# moisture_sensors.net
KiCad netlist of a schematic drawn in EAGLE
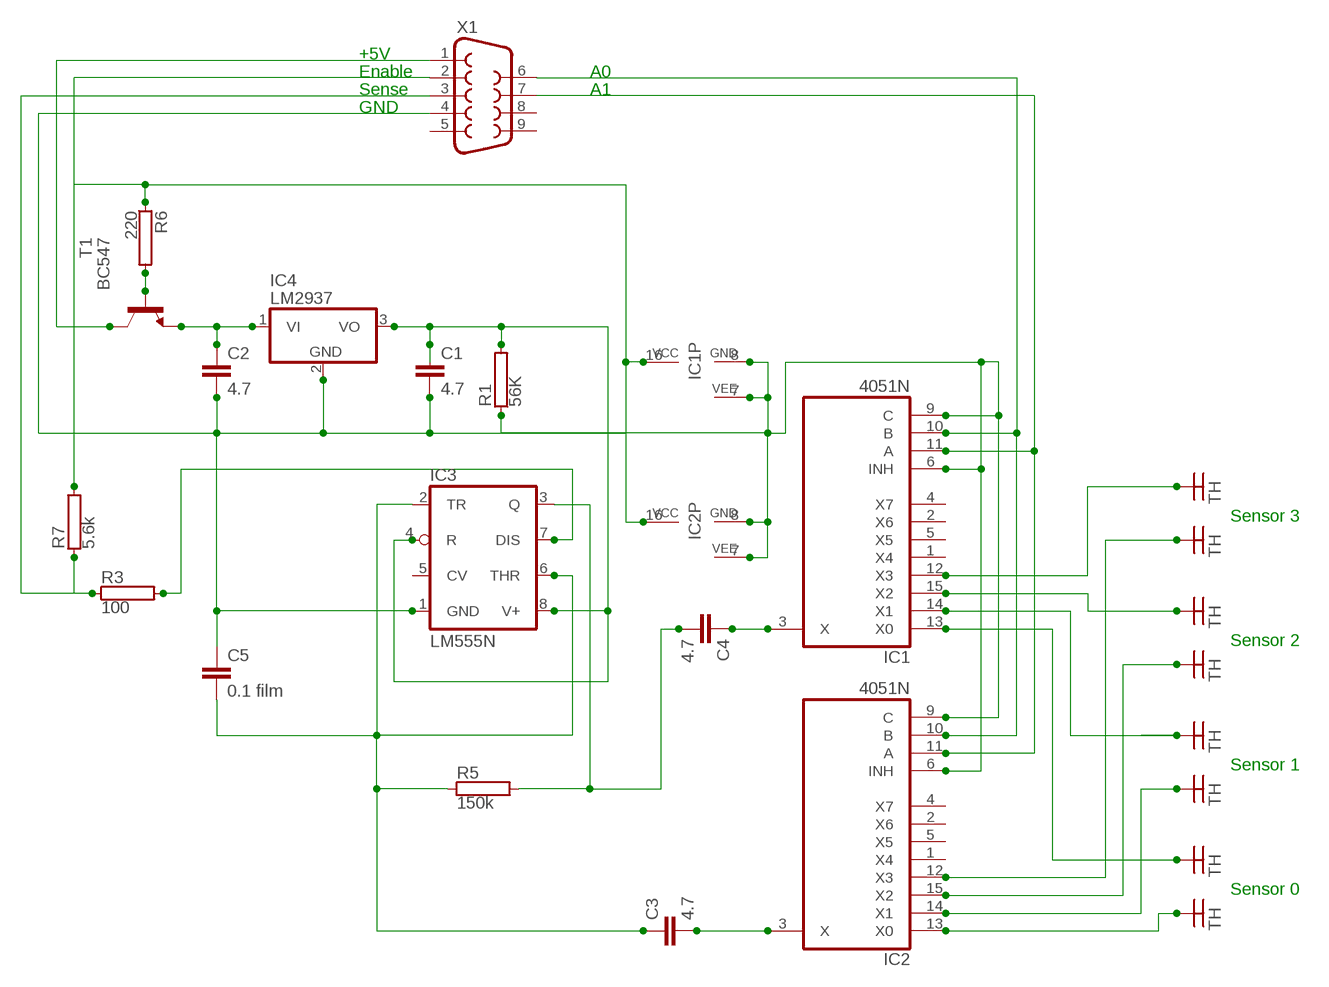
[diagram p0: schematic, sheet 1]

(export (version "E")
  (design (tool "Eeschema 10.0.6"))
  (components
    (comp (ref "C1")
      (value "4.7")
      (footprint "eagle-import:C2.5-3")
      (libsource (lib "eagle-import") (part "C2,5-3"))
    )
    (comp (ref "C2")
      (value "4.7")
      (footprint "eagle-import:C2.5-3")
      (libsource (lib "eagle-import") (part "C2,5-3"))
    )
    (comp (ref "C3")
      (value "4.7")
      (footprint "eagle-import:C2.5-3")
      (libsource (lib "eagle-import") (part "C2,5-3"))
    )
    (comp (ref "C4")
      (value "4.7")
      (footprint "eagle-import:C2.5-3")
      (libsource (lib "eagle-import") (part "C2,5-3"))
    )
    (comp (ref "C5")
      (value "0.1 film")
      (footprint "eagle-import:C2.5-3")
      (libsource (lib "eagle-import") (part "C2,5-3"))
    )
    (comp (ref "IC1")
      (value "4051N")
      (footprint "eagle-import:DIL16")
      (libsource (lib "eagle-import") (part "4051N"))
    )
    (comp (ref "IC2")
      (value "4051N")
      (footprint "eagle-import:DIL16")
      (libsource (lib "eagle-import") (part "4051N"))
    )
    (comp (ref "IC3")
      (value "LM555N")
      (footprint "eagle-import:DIL08")
      (libsource (lib "eagle-import") (part "555NLM"))
    )
    (comp (ref "IC4")
      (value "LM2937")
      (footprint "eagle-import:TO263-3")
      (libsource (lib "eagle-import") (part "LM2937"))
    )
    (comp (ref "R1")
      (value "56K")
      (footprint "eagle-import:AC01")
      (libsource (lib "eagle-import") (part "RAC01"))
    )
    (comp (ref "R3")
      (value "100")
      (footprint "eagle-import:AC01")
      (libsource (lib "eagle-import") (part "RAC01"))
    )
    (comp (ref "R5")
      (value "150k")
      (footprint "eagle-import:AC01")
      (libsource (lib "eagle-import") (part "RAC01"))
    )
    (comp (ref "R6")
      (value "220")
      (footprint "eagle-import:AC01")
      (libsource (lib "eagle-import") (part "RAC01"))
    )
    (comp (ref "R7")
      (value "5.6k")
      (footprint "eagle-import:AC01")
      (libsource (lib "eagle-import") (part "RAC01"))
    )
    (comp (ref "T1")
      (value "BC547")
      (footprint "eagle-import:TO92")
      (libsource (lib "eagle-import") (part "BC547"))
    )
    (comp (ref "X1")
      (value "DB9MALE")
      (footprint "eagle-import:DB9_MALE")
      (libsource (lib "eagle-import") (part "DB9MALE"))
    )
  )
  (nets
    (net (code "1") (name "Net-(IC1A-A)") (class "Default")
      (node (ref "IC1") (pin "11") (pinfunction "A_11") (pintype "input"))
      (node (ref "IC2") (pin "11") (pinfunction "A_11") (pintype "input"))
      (node (ref "X1") (pin "7") (pinfunction "7_7") (pintype "passive"))
    )
    (net (code "2") (name "Net-(IC1A-B)") (class "Default")
      (node (ref "IC1") (pin "10") (pinfunction "B_10") (pintype "input"))
      (node (ref "IC2") (pin "10") (pinfunction "B_10") (pintype "input"))
      (node (ref "X1") (pin "6") (pinfunction "6_6") (pintype "passive"))
    )
    (net (code "3") (name "Net-(IC1A-C)") (class "Default")
      (node (ref "C1") (pin "2") (pinfunction "2_2") (pintype "passive"))
      (node (ref "C2") (pin "2") (pinfunction "2_2") (pintype "passive"))
      (node (ref "C5") (pin "1") (pinfunction "1_1") (pintype "passive"))
      (node (ref "IC1") (pin "16") (pinfunction "VCC_16") (pintype "power_in"))
      (node (ref "IC1") (pin "6") (pinfunction "INH_6") (pintype "input"))
      (node (ref "IC1") (pin "7") (pinfunction "VEE_7") (pintype "power_in"))
      (node (ref "IC1") (pin "8") (pinfunction "GND_8") (pintype "power_in"))
      (node (ref "IC1") (pin "9") (pinfunction "C_9") (pintype "input"))
      (node (ref "IC2") (pin "16") (pinfunction "VCC_16") (pintype "power_in"))
      (node (ref "IC2") (pin "6") (pinfunction "INH_6") (pintype "input"))
      (node (ref "IC2") (pin "7") (pinfunction "VEE_7") (pintype "power_in"))
      (node (ref "IC2") (pin "8") (pinfunction "GND_8") (pintype "power_in"))
      (node (ref "IC2") (pin "9") (pinfunction "C_9") (pintype "input"))
      (node (ref "IC3") (pin "1") (pinfunction "GND_1") (pintype "power_in"))
      (node (ref "IC4") (pin "2") (pinfunction "GND_2") (pintype "passive"))
      (node (ref "R1") (pin "1") (pinfunction "1_1") (pintype "passive"))
      (node (ref "R6") (pin "1") (pinfunction "1_1") (pintype "passive"))
      (node (ref "R7") (pin "2") (pinfunction "2_2") (pintype "passive"))
      (node (ref "X1") (pin "2") (pinfunction "2_2") (pintype "passive"))
      (node (ref "X1") (pin "4") (pinfunction "4_4") (pintype "passive"))
    )
    (net (code "4") (name "Net-(IC1A-X)") (class "Default")
      (node (ref "C4") (pin "1") (pinfunction "1_1") (pintype "passive"))
      (node (ref "IC1") (pin "3") (pinfunction "X_3") (pintype "bidirectional"))
    )
    (net (code "5") (name "Net-(IC2A-X)") (class "Default")
      (node (ref "C3") (pin "2") (pinfunction "2_2") (pintype "passive"))
      (node (ref "IC2") (pin "3") (pinfunction "X_3") (pintype "bidirectional"))
    )
    (net (code "6") (name "Net-(IC3-DIS)") (class "Default")
      (node (ref "IC3") (pin "7") (pinfunction "DIS_7") (pintype "input"))
      (node (ref "R3") (pin "2") (pinfunction "2_2") (pintype "passive"))
    )
    (net (code "7") (name "Net-(IC3-Q)") (class "Default")
      (node (ref "C4") (pin "2") (pinfunction "2_2") (pintype "passive"))
      (node (ref "IC3") (pin "3") (pinfunction "Q_3") (pintype "output"))
      (node (ref "R5") (pin "2") (pinfunction "2_2") (pintype "passive"))
    )
    (net (code "8") (name "Net-(IC3-R)") (class "Default")
      (node (ref "C1") (pin "1") (pinfunction "1_1") (pintype "passive"))
      (node (ref "IC3") (pin "4") (pinfunction "R_4") (pintype "input"))
      (node (ref "IC3") (pin "8") (pinfunction "V+_8") (pintype "power_in"))
      (node (ref "IC4") (pin "3") (pinfunction "VO_3") (pintype "passive"))
      (node (ref "R1") (pin "2") (pinfunction "2_2") (pintype "passive"))
    )
    (net (code "9") (name "Net-(IC3-THR)") (class "Default")
      (node (ref "C3") (pin "1") (pinfunction "1_1") (pintype "passive"))
      (node (ref "C5") (pin "2") (pinfunction "2_2") (pintype "passive"))
      (node (ref "IC3") (pin "2") (pinfunction "TR_2") (pintype "input"))
      (node (ref "IC3") (pin "6") (pinfunction "THR_6") (pintype "input"))
      (node (ref "R5") (pin "1") (pinfunction "1_1") (pintype "passive"))
    )
    (net (code "10") (name "Net-(IC4-VI)") (class "Default")
      (node (ref "C2") (pin "1") (pinfunction "1_1") (pintype "passive"))
      (node (ref "IC4") (pin "1") (pinfunction "VI_1") (pintype "input"))
      (node (ref "T1") (pin "1") (pinfunction "E_1") (pintype "passive"))
    )
    (net (code "11") (name "Net-(R3-Pad1)") (class "Default")
      (node (ref "R3") (pin "1") (pinfunction "1_1") (pintype "passive"))
      (node (ref "R7") (pin "1") (pinfunction "1_1") (pintype "passive"))
      (node (ref "X1") (pin "3") (pinfunction "3_3") (pintype "passive"))
    )
    (net (code "12") (name "Net-(T1-B)") (class "Default")
      (node (ref "R6") (pin "2") (pinfunction "2_2") (pintype "passive"))
      (node (ref "T1") (pin "2") (pinfunction "B_2") (pintype "passive"))
    )
    (net (code "13") (name "Net-(T1-C)") (class "Default")
      (node (ref "T1") (pin "3") (pinfunction "C_3") (pintype "passive"))
      (node (ref "X1") (pin "1") (pinfunction "1_1") (pintype "passive"))
    )
    (net (code "14") (name "TH") (class "Default")
      (node (ref "IC1") (pin "12") (pinfunction "X3_12") (pintype "bidirectional"))
      (node (ref "IC1") (pin "13") (pinfunction "X0_13") (pintype "bidirectional"))
      (node (ref "IC1") (pin "14") (pinfunction "X1_14") (pintype "bidirectional"))
      (node (ref "IC1") (pin "15") (pinfunction "X2_15") (pintype "bidirectional"))
      (node (ref "IC2") (pin "12") (pinfunction "X3_12") (pintype "bidirectional"))
      (node (ref "IC2") (pin "13") (pinfunction "X0_13") (pintype "bidirectional"))
      (node (ref "IC2") (pin "14") (pinfunction "X1_14") (pintype "bidirectional"))
      (node (ref "IC2") (pin "15") (pinfunction "X2_15") (pintype "bidirectional"))
    )
    (net (code "15") (name "unconnected-(IC1A-X4-Pad1)") (class "Default")
      (node (ref "IC1") (pin "1") (pinfunction "X4_1") (pintype "bidirectional"))
    )
    (net (code "16") (name "unconnected-(IC1A-X5-Pad5)") (class "Default")
      (node (ref "IC1") (pin "5") (pinfunction "X5_5") (pintype "bidirectional"))
    )
    (net (code "17") (name "unconnected-(IC1A-X6-Pad2)") (class "Default")
      (node (ref "IC1") (pin "2") (pinfunction "X6_2") (pintype "bidirectional"))
    )
    (net (code "18") (name "unconnected-(IC1A-X7-Pad4)") (class "Default")
      (node (ref "IC1") (pin "4") (pinfunction "X7_4") (pintype "bidirectional"))
    )
    (net (code "19") (name "unconnected-(IC2A-X4-Pad1)") (class "Default")
      (node (ref "IC2") (pin "1") (pinfunction "X4_1") (pintype "bidirectional"))
    )
    (net (code "20") (name "unconnected-(IC2A-X5-Pad5)") (class "Default")
      (node (ref "IC2") (pin "5") (pinfunction "X5_5") (pintype "bidirectional"))
    )
    (net (code "21") (name "unconnected-(IC2A-X6-Pad2)") (class "Default")
      (node (ref "IC2") (pin "2") (pinfunction "X6_2") (pintype "bidirectional"))
    )
    (net (code "22") (name "unconnected-(IC2A-X7-Pad4)") (class "Default")
      (node (ref "IC2") (pin "4") (pinfunction "X7_4") (pintype "bidirectional"))
    )
    (net (code "23") (name "unconnected-(IC3-CV-Pad5)") (class "Default")
      (node (ref "IC3") (pin "5") (pinfunction "CV_5") (pintype "input"))
    )
    (net (code "24") (name "unconnected-(X1-Pad5)") (class "Default")
      (node (ref "X1") (pin "5") (pinfunction "5_5") (pintype "passive"))
    )
    (net (code "25") (name "unconnected-(X1-Pad8)") (class "Default")
      (node (ref "X1") (pin "8") (pinfunction "8_8") (pintype "passive"))
    )
    (net (code "26") (name "unconnected-(X1-Pad9)") (class "Default")
      (node (ref "X1") (pin "9") (pinfunction "9_9") (pintype "passive"))
    )
  )
)
